# Relay_Control.net
KiCad netlist of a schematic drawn in Altium Designer
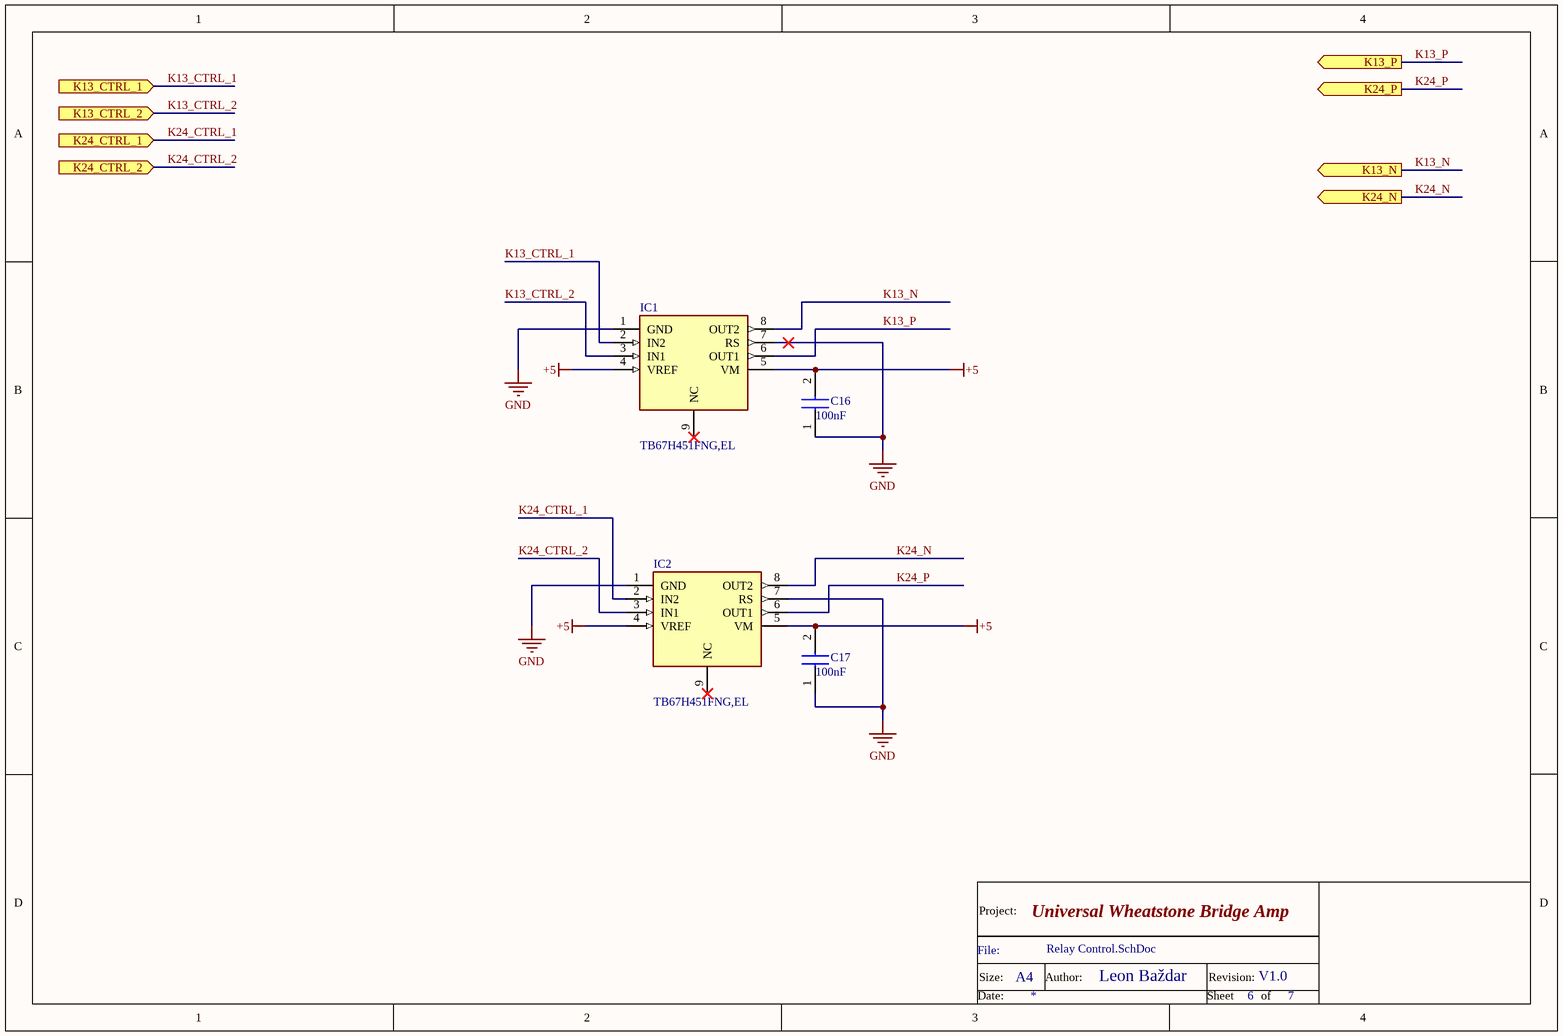
[diagram p0: Relay Control.SchDoc]

(export (version "E")
  (design (tool "Eeschema 10.0.6"))
  (components
    (comp (ref "C16")
      (value "100nF")
      (footprint "SamacSys:CAPC1005X55N")
      (description "Capacitor")
      (fields (field (name "MANUFACTURER_PART_NUMBER") "GCM155L81E104KE02D"))
      (libsource (lib "*") (part "GCM155L81E104KE02D"))
    )
    (comp (ref "C17")
      (value "100nF")
      (footprint "SamacSys:CAPC1005X55N")
      (description "Capacitor")
      (fields (field (name "MANUFACTURER_PART_NUMBER") "GCM155L81E104KE02D"))
      (libsource (lib "*") (part "GCM155L81E104KE02D"))
    )
    (comp (ref "IC1")
      (value "TB67H451FNG,EL")
      (footprint "SamacSys:SOIC127P600X170-9N")
      (description "Integrated Circuit")
      (libsource (lib "*") (part "TB67H451FNG,EL"))
    )
    (comp (ref "IC2")
      (value "TB67H451FNG,EL")
      (footprint "SamacSys:SOIC127P600X170-9N")
      (description "Integrated Circuit")
      (libsource (lib "*") (part "TB67H451FNG,EL"))
    )
  )
  (nets
    (net (code "1") (name "+5") (class "Default")
      (node (ref "C16") (pin "2") (pinfunction "2_2") (pintype "passive"))
      (node (ref "C17") (pin "2") (pinfunction "2_2") (pintype "passive"))
      (node (ref "IC1") (pin "4") (pinfunction "VREF_4") (pintype "input"))
      (node (ref "IC1") (pin "5") (pinfunction "VM_5") (pintype "power_in"))
      (node (ref "IC2") (pin "4") (pinfunction "VREF_4") (pintype "input"))
      (node (ref "IC2") (pin "5") (pinfunction "VM_5") (pintype "power_in"))
    )
    (net (code "2") (name "/K13_CTRL_1") (class "Default")
      (node (ref "IC1") (pin "2") (pinfunction "IN2_2") (pintype "input"))
    )
    (net (code "3") (name "/K13_CTRL_2") (class "Default")
      (node (ref "IC1") (pin "3") (pinfunction "IN1_3") (pintype "input"))
    )
    (net (code "4") (name "/K13_N") (class "Default")
      (node (ref "IC1") (pin "8") (pinfunction "OUT2_8") (pintype "output"))
    )
    (net (code "5") (name "/K13_P") (class "Default")
      (node (ref "IC1") (pin "6") (pinfunction "OUT1_6") (pintype "output"))
    )
    (net (code "6") (name "/K24_CTRL_1") (class "Default")
      (node (ref "IC2") (pin "2") (pinfunction "IN2_2") (pintype "input"))
    )
    (net (code "7") (name "/K24_CTRL_2") (class "Default")
      (node (ref "IC2") (pin "3") (pinfunction "IN1_3") (pintype "input"))
    )
    (net (code "8") (name "/K24_N") (class "Default")
      (node (ref "IC2") (pin "8") (pinfunction "OUT2_8") (pintype "output"))
    )
    (net (code "9") (name "/K24_P") (class "Default")
      (node (ref "IC2") (pin "6") (pinfunction "OUT1_6") (pintype "output"))
    )
    (net (code "10") (name "GND") (class "Default")
      (node (ref "C16") (pin "1") (pinfunction "1_1") (pintype "passive"))
      (node (ref "C17") (pin "1") (pinfunction "1_1") (pintype "passive"))
      (node (ref "IC1") (pin "1") (pinfunction "GND_1") (pintype "power_in"))
      (node (ref "IC1") (pin "7") (pinfunction "RS_7") (pintype "output"))
      (node (ref "IC2") (pin "1") (pinfunction "GND_1") (pintype "power_in"))
      (node (ref "IC2") (pin "7") (pinfunction "RS_7") (pintype "output"))
    )
    (net (code "11") (name "unconnected-(IC1-NC-Pad9)") (class "Default")
      (node (ref "IC1") (pin "9") (pinfunction "NC_9") (pintype "passive+no_connect"))
    )
    (net (code "12") (name "unconnected-(IC2-NC-Pad9)") (class "Default")
      (node (ref "IC2") (pin "9") (pinfunction "NC_9") (pintype "passive+no_connect"))
    )
  )
)
